# MCU.net
KiCad netlist of a schematic drawn in Altium Designer
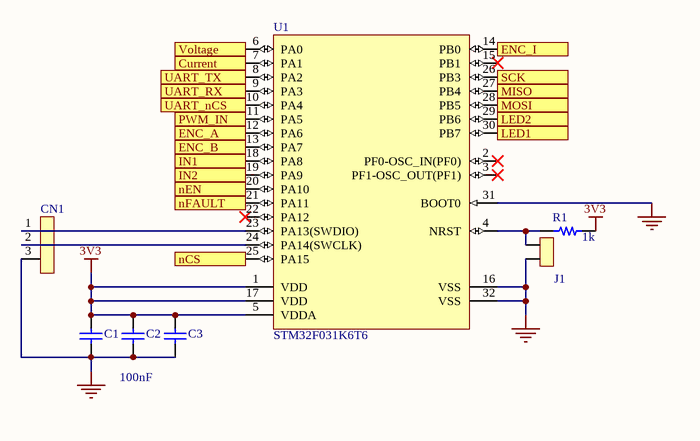
[diagram p0: MCU.SchDoc]

(export (version "E")
  (design (tool "Eeschema 10.0.6"))
  (components
    (comp (ref "C1")
      (value "Cap")
      (footprint "0402")
      (fields (field (name "PUBLISHER") "Altium Limited"))
      (libsource (lib "Parts") (part "Cap"))
    )
    (comp (ref "C2")
      (value "100nF")
      (footprint "0402")
      (fields (field (name "Comment") "Cap") (field (name "PUBLISHER") "Altium Limited"))
      (libsource (lib "Parts") (part "Cap"))
    )
    (comp (ref "C3")
      (value "Cap")
      (footprint "0402")
      (fields (field (name "PUBLISHER") "Altium Limited"))
      (libsource (lib "Parts") (part "Cap"))
    )
    (comp (ref "CN1") (value "3P-2.5mm") (footprint "2.5mm-3P") (libsource (lib "Parts") (part "3P-2.5mm")))
    (comp (ref "J1") (value "Jumper") (footprint "Jumper") (libsource (lib "Parts") (part "Jumper")))
    (comp (ref "R1") (value "1k") (footprint "0805 - duplicate") (libsource (lib "Parts") (part "Resistor")))
    (comp (ref "U1")
      (value "STM32F031K6T6")
      (footprint "STM-LQFP32_N")
      (fields (field (name "MANUFACTURER") "STMicroelectronics"))
      (libsource (lib "Altium Content Vault") (part "MC-ARM-STM32F0XX-LQFP32"))
    )
  )
  (nets
    (net (code "1") (name "/Current") (class "Default")
      (node (ref "U1") (pin "7") (pinfunction "PA1_7") (pintype "bidirectional"))
    )
    (net (code "2") (name "/ENC_A") (class "Default")
      (node (ref "U1") (pin "12") (pinfunction "PA6_12") (pintype "bidirectional"))
    )
    (net (code "3") (name "/ENC_B") (class "Default")
      (node (ref "U1") (pin "13") (pinfunction "PA7_13") (pintype "bidirectional"))
    )
    (net (code "4") (name "/ENC_I") (class "Default")
      (node (ref "U1") (pin "14") (pinfunction "PB0_14") (pintype "bidirectional"))
    )
    (net (code "5") (name "/IN1") (class "Default")
      (node (ref "U1") (pin "18") (pinfunction "PA8_18") (pintype "bidirectional"))
    )
    (net (code "6") (name "/IN2") (class "Default")
      (node (ref "U1") (pin "19") (pinfunction "PA9_19") (pintype "bidirectional"))
    )
    (net (code "7") (name "/LED1") (class "Default")
      (node (ref "U1") (pin "30") (pinfunction "PB7_30") (pintype "bidirectional"))
    )
    (net (code "8") (name "/LED2") (class "Default")
      (node (ref "U1") (pin "29") (pinfunction "PB6_29") (pintype "bidirectional"))
    )
    (net (code "9") (name "/MISO") (class "Default")
      (node (ref "U1") (pin "27") (pinfunction "PB4_27") (pintype "bidirectional"))
    )
    (net (code "10") (name "/MOSI") (class "Default")
      (node (ref "U1") (pin "28") (pinfunction "PB5_28") (pintype "bidirectional"))
    )
    (net (code "11") (name "/PWM_IN") (class "Default")
      (node (ref "U1") (pin "11") (pinfunction "PA5_11") (pintype "bidirectional"))
    )
    (net (code "12") (name "/SCK") (class "Default")
      (node (ref "U1") (pin "26") (pinfunction "PB3_26") (pintype "bidirectional"))
    )
    (net (code "13") (name "/UART_RX") (class "Default")
      (node (ref "U1") (pin "9") (pinfunction "PA3_9") (pintype "bidirectional"))
    )
    (net (code "14") (name "/UART_TX") (class "Default")
      (node (ref "U1") (pin "8") (pinfunction "PA2_8") (pintype "bidirectional"))
    )
    (net (code "15") (name "/UART_nCS") (class "Default")
      (node (ref "U1") (pin "10") (pinfunction "PA4_10") (pintype "bidirectional"))
    )
    (net (code "16") (name "/Voltage") (class "Default")
      (node (ref "U1") (pin "6") (pinfunction "PA0_6") (pintype "bidirectional"))
    )
    (net (code "17") (name "/nCS") (class "Default")
      (node (ref "U1") (pin "25") (pinfunction "PA15_25") (pintype "bidirectional"))
    )
    (net (code "18") (name "/nEN") (class "Default")
      (node (ref "U1") (pin "20") (pinfunction "PA10_20") (pintype "bidirectional"))
    )
    (net (code "19") (name "/nFAULT") (class "Default")
      (node (ref "U1") (pin "21") (pinfunction "PA11_21") (pintype "bidirectional"))
    )
    (net (code "20") (name "3V3") (class "Default")
      (node (ref "C1") (pin "2") (pinfunction "2_2") (pintype "passive"))
      (node (ref "C2") (pin "2") (pinfunction "2_2") (pintype "passive"))
      (node (ref "C3") (pin "2") (pinfunction "2_2") (pintype "passive"))
      (node (ref "R1") (pin "2") (pinfunction "2_2") (pintype "passive"))
      (node (ref "U1") (pin "1") (pinfunction "VDD_1") (pintype "power_in"))
      (node (ref "U1") (pin "17") (pinfunction "VDD_17") (pintype "power_in"))
      (node (ref "U1") (pin "5") (pinfunction "VDDA_5") (pintype "power_in"))
    )
    (net (code "21") (name "GND") (class "Default")
      (node (ref "C1") (pin "1") (pinfunction "1_1") (pintype "passive"))
      (node (ref "C2") (pin "1") (pinfunction "1_1") (pintype "passive"))
      (node (ref "C3") (pin "1") (pinfunction "1_1") (pintype "passive"))
      (node (ref "CN1") (pin "3") (pintype "passive"))
      (node (ref "J1") (pin "2") (pintype "passive"))
      (node (ref "U1") (pin "16") (pinfunction "VSS_16") (pintype "power_in"))
      (node (ref "U1") (pin "31") (pinfunction "BOOT0_31") (pintype "input"))
      (node (ref "U1") (pin "32") (pinfunction "VSS_32") (pintype "power_in"))
    )
    (net (code "22") (name "Net-(U1-NRST)") (class "Default")
      (node (ref "J1") (pin "1") (pintype "passive"))
      (node (ref "R1") (pin "1") (pinfunction "1_1") (pintype "passive"))
      (node (ref "U1") (pin "4") (pinfunction "NRST_4") (pintype "bidirectional"))
    )
    (net (code "23") (name "Net-(U1-PA13(SWDIO))") (class "Default")
      (node (ref "CN1") (pin "1") (pintype "passive"))
      (node (ref "U1") (pin "23") (pinfunction "PA13(SWDIO)_23") (pintype "bidirectional"))
    )
    (net (code "24") (name "Net-(U1-PA14(SWCLK))") (class "Default")
      (node (ref "CN1") (pin "2") (pintype "passive"))
      (node (ref "U1") (pin "24") (pinfunction "PA14(SWCLK)_24") (pintype "bidirectional"))
    )
    (net (code "25") (name "unconnected-(U1-PA12-Pad22)") (class "Default")
      (node (ref "U1") (pin "22") (pinfunction "PA12_22") (pintype "bidirectional+no_connect"))
    )
    (net (code "26") (name "unconnected-(U1-PB1-Pad15)") (class "Default")
      (node (ref "U1") (pin "15") (pinfunction "PB1_15") (pintype "bidirectional+no_connect"))
    )
    (net (code "27") (name "unconnected-(U1-PF0-OSC_IN(PF0)-Pad2)") (class "Default")
      (node (ref "U1") (pin "2") (pinfunction "PF0-OSC_IN(PF0)_2") (pintype "bidirectional+no_connect"))
    )
    (net (code "28") (name "unconnected-(U1-PF1-OSC_OUT(PF1)-Pad3)") (class "Default")
      (node (ref "U1") (pin "3") (pinfunction "PF1-OSC_OUT(PF1)_3") (pintype "bidirectional+no_connect"))
    )
  )
)
